# Page_05-LAN9254-Part2.net
KiCad netlist of a schematic drawn in Altium Designer
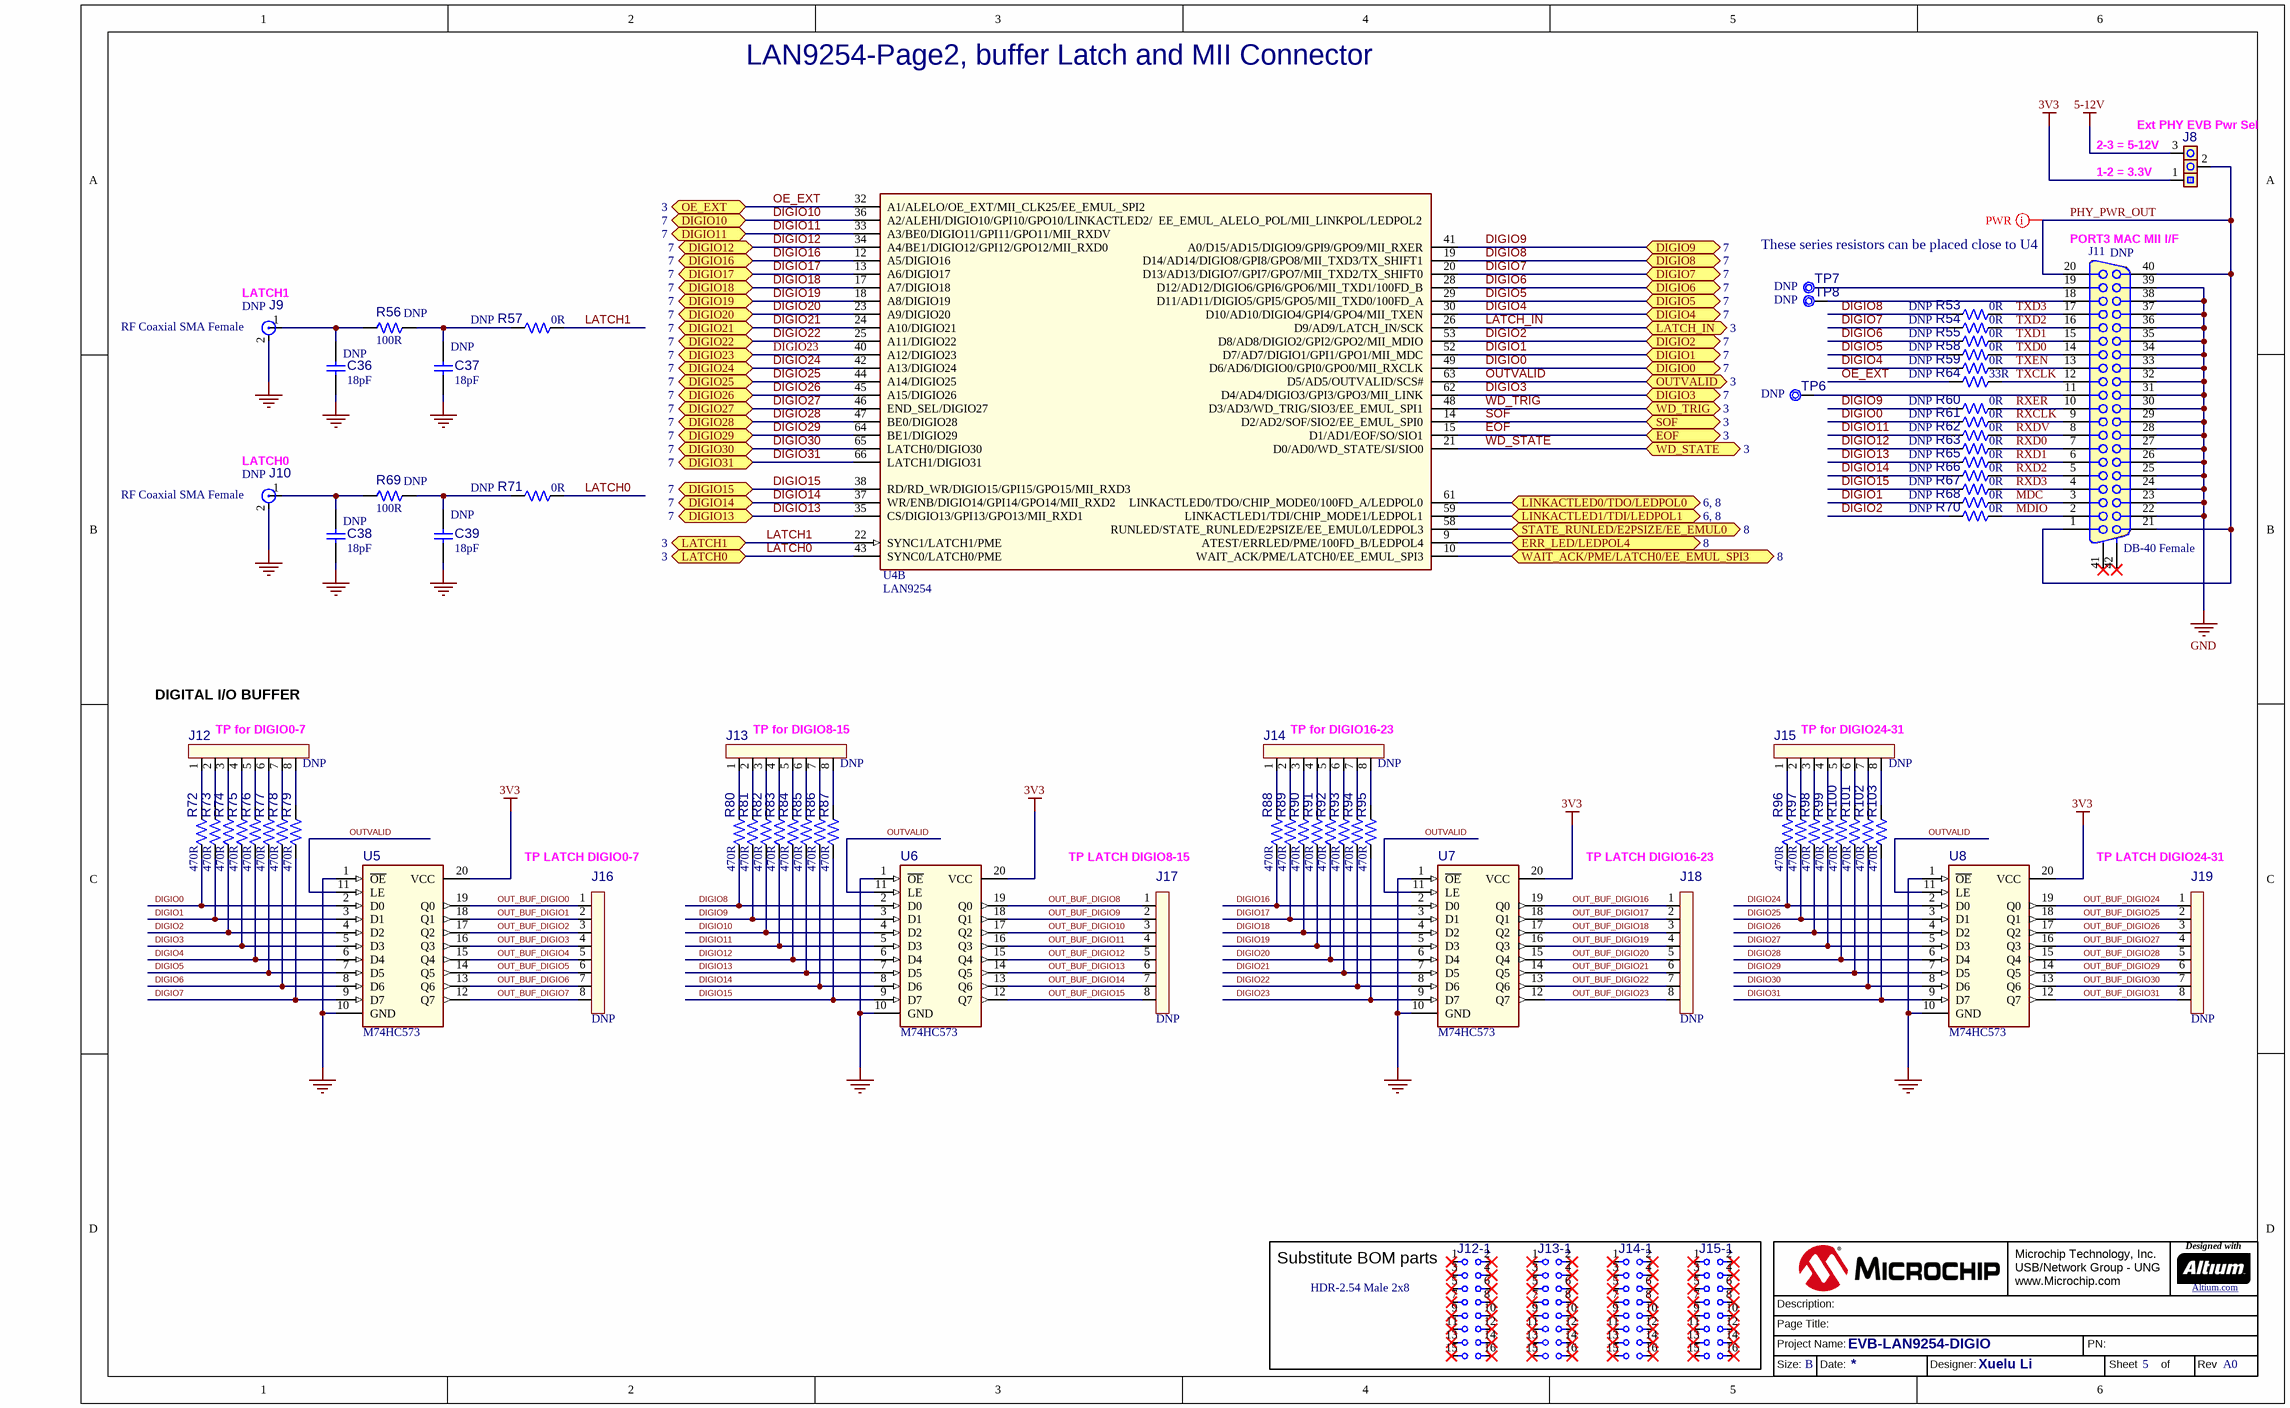
[diagram p0: Page 05-LAN9254-Part2.SchDoc]

(export (version "E")
  (design (tool "Eeschema 10.0.6"))
  (components
    (comp (ref "C36")
      (value "18pF")
      (footprint "CAP_C_0805")
      (description "Capacitor")
      (fields (field (name "VOLTAGE") "50V") (field (name "TOLERANCE") "5%") (field (name "POPULATED") "DNP"))
      (libsource (lib "MCHP-CDB") (part "Capacitor NP"))
    )
    (comp (ref "C37")
      (value "18pF")
      (footprint "CAP_C_0805")
      (description "Capacitor")
      (fields (field (name "VOLTAGE") "50V") (field (name "TOLERANCE") "5%") (field (name "POPULATED") "DNP"))
      (libsource (lib "MCHP-CDB") (part "Capacitor NP"))
    )
    (comp (ref "C38")
      (value "18pF")
      (footprint "CAP_C_0805")
      (description "Capacitor")
      (fields (field (name "VOLTAGE") "50V") (field (name "TOLERANCE") "5%") (field (name "POPULATED") "DNP"))
      (libsource (lib "MCHP-CDB") (part "Capacitor NP"))
    )
    (comp (ref "C39")
      (value "18pF")
      (footprint "CAP_C_0805")
      (description "Capacitor")
      (fields (field (name "VOLTAGE") "50V") (field (name "TOLERANCE") "5%") (field (name "POPULATED") "DNP"))
      (libsource (lib "MCHP-CDB") (part "Capacitor NP"))
    )
    (comp (ref "J8")
      (value "Header 1x3")
      (footprint "HDR_M_2.54_1x3")
      (libsource (lib "MCHP-CDB") (part "Header 1x3"))
    )
    (comp (ref "J9")
      (value "RF Coaxial SMA Female")
      (footprint "CON_JACK_F_TH_V_ACP_901-144-8RFX")
      (description "CON Jack 2 Pins")
      (fields (field (name "POPULATED") "DNP") (field (name "OWNER") "Jairuz Agang-ang"))
      (libsource (lib "MCHP-CDB") (part "CON Jack 2 Pins"))
    )
    (comp (ref "J10")
      (value "RF Coaxial SMA Female")
      (footprint "CON_JACK_F_TH_V_ACP_901-144-8RFX")
      (description "CON Jack 2 Pins")
      (fields (field (name "POPULATED") "DNP") (field (name "OWNER") "Jairuz Agang-ang"))
      (libsource (lib "MCHP-CDB") (part "CON Jack 2 Pins"))
    )
    (comp (ref "J11")
      (value "DB-40 Female")
      (footprint "CON_DSUB40_TH_RA_F")
      (fields
        (field (name "VOLTAGE") "30V")
        (field (name "POPULATED") "DNP")
        (field (name "Comment") "CON DB-40")
        (field (name "OWNER") "Sam Charles")
      )
      (libsource (lib "MCHP-CDB") (part "CON DB-40"))
    )
    (comp (ref "J12")
      (value "HDR_M_2.54_1x8-doubled")
      (footprint "HDR_M_2.54_1x8-doubled")
      (description "CON HDR-2.54 Female 1x8 Gold TH")
      (fields (field (name "POPULATED") "DNP"))
      (libsource (lib "") (part "Header 1x8_1"))
    )
    (comp (ref "J12-1")
      (value "HDR-2.54 Male 2x8")
      (footprint "HDR_M_2.54_2x8")
      (fields (field (name "Comment") "Header 2x8") (field (name "OWNER") "Brent Lanphear"))
      (libsource (lib "MCHP-CDB-Offline") (part "Header 2x8"))
    )
    (comp (ref "J13")
      (value "HDR_M_2.54_1x8-doubled")
      (footprint "HDR_M_2.54_1x8-doubled")
      (description "CON HDR-2.54 Female 1x8 Gold TH")
      (fields (field (name "POPULATED") "DNP"))
      (libsource (lib "") (part "Header 1x8_1"))
    )
    (comp (ref "J13-1")
      (value "Header 2x8")
      (footprint "HDR_M_2.54_2x8")
      (fields (field (name "OWNER") "Brent Lanphear"))
      (libsource (lib "MCHP-CDB-Offline") (part "Header 2x8"))
    )
    (comp (ref "J14")
      (value "HDR_M_2.54_1x8-doubled")
      (footprint "HDR_M_2.54_1x8-doubled")
      (description "CON HDR-2.54 Female 1x8 Gold TH")
      (fields (field (name "POPULATED") "DNP"))
      (libsource (lib "") (part "Header 1x8_1"))
    )
    (comp (ref "J14-1")
      (value "Header 2x8")
      (footprint "HDR_M_2.54_2x8")
      (fields (field (name "OWNER") "Brent Lanphear"))
      (libsource (lib "MCHP-CDB-Offline") (part "Header 2x8"))
    )
    (comp (ref "J15")
      (value "HDR_M_2.54_1x8-doubled")
      (footprint "HDR_M_2.54_1x8-doubled")
      (description "CON HDR-2.54 Female 1x8 Gold TH")
      (fields (field (name "POPULATED") "DNP"))
      (libsource (lib "") (part "Header 1x8_1"))
    )
    (comp (ref "J15-1")
      (value "Header 2x8")
      (footprint "HDR_M_2.54_2x8")
      (fields (field (name "OWNER") "Brent Lanphear"))
      (libsource (lib "MCHP-CDB-Offline") (part "Header 2x8"))
    )
    (comp (ref "J16")
      (value "HDR_M_2.54_1x8-stripped")
      (footprint "HDR_M_2.54_1x8-stripped")
      (description "CON HDR-2.54 Female 1x8 Gold TH")
      (fields (field (name "POPULATED") "DNP"))
      (libsource (lib "MCHP-CDB") (part "Header 1x8"))
    )
    (comp (ref "J17")
      (value "HDR_M_2.54_1x8-stripped")
      (footprint "HDR_M_2.54_1x8-stripped")
      (description "CON HDR-2.54 Female 1x8 Gold TH")
      (fields (field (name "POPULATED") "DNP"))
      (libsource (lib "MCHP-CDB") (part "Header 1x8"))
    )
    (comp (ref "J18")
      (value "HDR_M_2.54_1x8-stripped")
      (footprint "HDR_M_2.54_1x8-stripped")
      (description "CON HDR-2.54 Female 1x8 Gold TH")
      (fields (field (name "POPULATED") "DNP"))
      (libsource (lib "MCHP-CDB") (part "Header 1x8"))
    )
    (comp (ref "J19")
      (value "HDR_M_2.54_1x8-stripped")
      (footprint "HDR_M_2.54_1x8-stripped")
      (description "CON HDR-2.54 Female 1x8 Gold TH")
      (fields (field (name "POPULATED") "DNP"))
      (libsource (lib "MCHP-CDB") (part "Header 1x8"))
    )
    (comp (ref "R53")
      (value "0R")
      (footprint "RES_C_0402")
      (description "Resistor")
      (fields
        (field (name "POWER") "1/16W")
        (field (name "POPULATED") "DNP")
        (field (name "OWNER") "Sompoch Loboonlert")
      )
      (libsource (lib "MCHP-CDB") (part "Resistor"))
    )
    (comp (ref "R54")
      (value "0R")
      (footprint "RES_C_0402")
      (description "Resistor")
      (fields
        (field (name "POWER") "1/16W")
        (field (name "POPULATED") "DNP")
        (field (name "OWNER") "Sompoch Loboonlert")
      )
      (libsource (lib "MCHP-CDB") (part "Resistor"))
    )
    (comp (ref "R55")
      (value "0R")
      (footprint "RES_C_0402")
      (description "Resistor")
      (fields
        (field (name "POWER") "1/16W")
        (field (name "POPULATED") "DNP")
        (field (name "OWNER") "Sompoch Loboonlert")
      )
      (libsource (lib "MCHP-CDB") (part "Resistor"))
    )
    (comp (ref "R56")
      (value "100R")
      (footprint "RES_C_0805")
      (description "Resistor")
      (fields
        (field (name "TOLERANCE") "5%")
        (field (name "POWER") "1/10W")
        (field (name "POPULATED") "DNP")
        (field (name "OWNER") "Jairuz Agang-ang")
      )
      (libsource (lib "MCHP-CDB") (part "Resistor"))
    )
    (comp (ref "R57")
      (value "0R")
      (footprint "RES_C_0402")
      (description "Resistor")
      (fields
        (field (name "POWER") "1/16W")
        (field (name "POPULATED") "DNP")
        (field (name "OWNER") "Sompoch Loboonlert")
      )
      (libsource (lib "MCHP-CDB") (part "Resistor"))
    )
    (comp (ref "R58")
      (value "0R")
      (footprint "RES_C_0402")
      (description "Resistor")
      (fields
        (field (name "POWER") "1/16W")
        (field (name "POPULATED") "DNP")
        (field (name "OWNER") "Sompoch Loboonlert")
      )
      (libsource (lib "MCHP-CDB") (part "Resistor"))
    )
    (comp (ref "R59")
      (value "0R")
      (footprint "RES_C_0402")
      (description "Resistor")
      (fields
        (field (name "POWER") "1/16W")
        (field (name "POPULATED") "DNP")
        (field (name "OWNER") "Sompoch Loboonlert")
      )
      (libsource (lib "MCHP-CDB") (part "Resistor"))
    )
    (comp (ref "R60")
      (value "0R")
      (footprint "RES_C_0402")
      (description "Resistor")
      (fields
        (field (name "POWER") "1/16W")
        (field (name "POPULATED") "DNP")
        (field (name "OWNER") "Sompoch Loboonlert")
      )
      (libsource (lib "MCHP-CDB") (part "Resistor"))
    )
    (comp (ref "R61")
      (value "0R")
      (footprint "RES_C_0402")
      (description "Resistor")
      (fields
        (field (name "POWER") "1/16W")
        (field (name "POPULATED") "DNP")
        (field (name "OWNER") "Sompoch Loboonlert")
      )
      (libsource (lib "MCHP-CDB") (part "Resistor"))
    )
    (comp (ref "R62")
      (value "0R")
      (footprint "RES_C_0402")
      (description "Resistor")
      (fields
        (field (name "POWER") "1/16W")
        (field (name "POPULATED") "DNP")
        (field (name "OWNER") "Sompoch Loboonlert")
      )
      (libsource (lib "MCHP-CDB") (part "Resistor"))
    )
    (comp (ref "R63")
      (value "0R")
      (footprint "RES_C_0402")
      (description "Resistor")
      (fields
        (field (name "POWER") "1/16W")
        (field (name "POPULATED") "DNP")
        (field (name "OWNER") "Sompoch Loboonlert")
      )
      (libsource (lib "MCHP-CDB") (part "Resistor"))
    )
    (comp (ref "R64")
      (value "33R")
      (footprint "RES_C_0402")
      (description "Resistor")
      (fields
        (field (name "TOLERANCE") "1%")
        (field (name "VOLTAGE") "50V")
        (field (name "POPULATED") "DNP")
        (field (name "OWNER") "Mike Ragsdale")
      )
      (libsource (lib "MCHP-CDB") (part "Resistor"))
    )
    (comp (ref "R65")
      (value "0R")
      (footprint "RES_C_0402")
      (description "Resistor")
      (fields
        (field (name "POWER") "1/16W")
        (field (name "POPULATED") "DNP")
        (field (name "OWNER") "Sompoch Loboonlert")
      )
      (libsource (lib "MCHP-CDB") (part "Resistor"))
    )
    (comp (ref "R66")
      (value "0R")
      (footprint "RES_C_0402")
      (description "Resistor")
      (fields
        (field (name "POWER") "1/16W")
        (field (name "POPULATED") "DNP")
        (field (name "OWNER") "Sompoch Loboonlert")
      )
      (libsource (lib "MCHP-CDB") (part "Resistor"))
    )
    (comp (ref "R67")
      (value "0R")
      (footprint "RES_C_0402")
      (description "Resistor")
      (fields
        (field (name "POWER") "1/16W")
        (field (name "POPULATED") "DNP")
        (field (name "OWNER") "Sompoch Loboonlert")
      )
      (libsource (lib "MCHP-CDB") (part "Resistor"))
    )
    (comp (ref "R68")
      (value "0R")
      (footprint "RES_C_0402")
      (description "Resistor")
      (fields
        (field (name "POWER") "1/16W")
        (field (name "POPULATED") "DNP")
        (field (name "OWNER") "Sompoch Loboonlert")
      )
      (libsource (lib "MCHP-CDB") (part "Resistor"))
    )
    (comp (ref "R69")
      (value "100R")
      (footprint "RES_C_0805")
      (description "Resistor")
      (fields
        (field (name "TOLERANCE") "5%")
        (field (name "POWER") "1/10W")
        (field (name "POPULATED") "DNP")
        (field (name "OWNER") "Jairuz Agang-ang")
      )
      (libsource (lib "MCHP-CDB") (part "Resistor"))
    )
    (comp (ref "R70")
      (value "0R")
      (footprint "RES_C_0402")
      (description "Resistor")
      (fields
        (field (name "POWER") "1/16W")
        (field (name "POPULATED") "DNP")
        (field (name "OWNER") "Sompoch Loboonlert")
      )
      (libsource (lib "MCHP-CDB") (part "Resistor"))
    )
    (comp (ref "R71")
      (value "0R")
      (footprint "RES_C_0402")
      (description "Resistor")
      (fields
        (field (name "POWER") "1/16W")
        (field (name "POPULATED") "DNP")
        (field (name "OWNER") "Sompoch Loboonlert")
      )
      (libsource (lib "MCHP-CDB") (part "Resistor"))
    )
    (comp (ref "R72")
      (value "470R")
      (footprint "RES_C_0402")
      (description "Resistor")
      (fields (field (name "TOLERANCE") "5%") (field (name "VOLTAGE") "50V"))
      (libsource (lib "MCHP-CDB") (part "Resistor"))
    )
    (comp (ref "R73")
      (value "470R")
      (footprint "RES_C_0402")
      (description "Resistor")
      (fields (field (name "TOLERANCE") "5%") (field (name "VOLTAGE") "50V"))
      (libsource (lib "MCHP-CDB") (part "Resistor"))
    )
    (comp (ref "R74")
      (value "470R")
      (footprint "RES_C_0402")
      (description "Resistor")
      (fields (field (name "TOLERANCE") "5%") (field (name "VOLTAGE") "50V"))
      (libsource (lib "MCHP-CDB") (part "Resistor"))
    )
    (comp (ref "R75")
      (value "470R")
      (footprint "RES_C_0402")
      (description "Resistor")
      (fields (field (name "TOLERANCE") "5%") (field (name "VOLTAGE") "50V"))
      (libsource (lib "MCHP-CDB") (part "Resistor"))
    )
    (comp (ref "R76")
      (value "470R")
      (footprint "RES_C_0402")
      (description "Resistor")
      (fields (field (name "TOLERANCE") "5%") (field (name "VOLTAGE") "50V"))
      (libsource (lib "MCHP-CDB") (part "Resistor"))
    )
    (comp (ref "R77")
      (value "470R")
      (footprint "RES_C_0402")
      (description "Resistor")
      (fields (field (name "TOLERANCE") "5%") (field (name "VOLTAGE") "50V"))
      (libsource (lib "MCHP-CDB") (part "Resistor"))
    )
    (comp (ref "R78")
      (value "470R")
      (footprint "RES_C_0402")
      (description "Resistor")
      (fields (field (name "TOLERANCE") "5%") (field (name "VOLTAGE") "50V"))
      (libsource (lib "MCHP-CDB") (part "Resistor"))
    )
    (comp (ref "R79")
      (value "470R")
      (footprint "RES_C_0402")
      (description "Resistor")
      (fields (field (name "TOLERANCE") "5%") (field (name "VOLTAGE") "50V"))
      (libsource (lib "MCHP-CDB") (part "Resistor"))
    )
    (comp (ref "R80")
      (value "470R")
      (footprint "RES_C_0402")
      (description "Resistor")
      (fields (field (name "TOLERANCE") "5%") (field (name "VOLTAGE") "50V"))
      (libsource (lib "MCHP-CDB") (part "Resistor"))
    )
    (comp (ref "R81")
      (value "470R")
      (footprint "RES_C_0402")
      (description "Resistor")
      (fields (field (name "TOLERANCE") "5%") (field (name "VOLTAGE") "50V"))
      (libsource (lib "MCHP-CDB") (part "Resistor"))
    )
    (comp (ref "R82")
      (value "470R")
      (footprint "RES_C_0402")
      (description "Resistor")
      (fields (field (name "TOLERANCE") "5%") (field (name "VOLTAGE") "50V"))
      (libsource (lib "MCHP-CDB") (part "Resistor"))
    )
    (comp (ref "R83")
      (value "470R")
      (footprint "RES_C_0402")
      (description "Resistor")
      (fields (field (name "TOLERANCE") "5%") (field (name "VOLTAGE") "50V"))
      (libsource (lib "MCHP-CDB") (part "Resistor"))
    )
    (comp (ref "R84")
      (value "470R")
      (footprint "RES_C_0402")
      (description "Resistor")
      (fields (field (name "TOLERANCE") "5%") (field (name "VOLTAGE") "50V"))
      (libsource (lib "MCHP-CDB") (part "Resistor"))
    )
    (comp (ref "R85")
      (value "470R")
      (footprint "RES_C_0402")
      (description "Resistor")
      (fields (field (name "TOLERANCE") "5%") (field (name "VOLTAGE") "50V"))
      (libsource (lib "MCHP-CDB") (part "Resistor"))
    )
    (comp (ref "R86")
      (value "470R")
      (footprint "RES_C_0402")
      (description "Resistor")
      (fields (field (name "TOLERANCE") "5%") (field (name "VOLTAGE") "50V"))
      (libsource (lib "MCHP-CDB") (part "Resistor"))
    )
    (comp (ref "R87")
      (value "470R")
      (footprint "RES_C_0402")
      (description "Resistor")
      (fields (field (name "TOLERANCE") "5%") (field (name "VOLTAGE") "50V"))
      (libsource (lib "MCHP-CDB") (part "Resistor"))
    )
    (comp (ref "R88")
      (value "470R")
      (footprint "RES_C_0402")
      (description "Resistor")
      (fields (field (name "TOLERANCE") "5%") (field (name "VOLTAGE") "50V"))
      (libsource (lib "MCHP-CDB") (part "Resistor"))
    )
    (comp (ref "R89")
      (value "470R")
      (footprint "RES_C_0402")
      (description "Resistor")
      (fields (field (name "TOLERANCE") "5%") (field (name "VOLTAGE") "50V"))
      (libsource (lib "MCHP-CDB") (part "Resistor"))
    )
    (comp (ref "R90")
      (value "470R")
      (footprint "RES_C_0402")
      (description "Resistor")
      (fields (field (name "TOLERANCE") "5%") (field (name "VOLTAGE") "50V"))
      (libsource (lib "MCHP-CDB") (part "Resistor"))
    )
    (comp (ref "R91")
      (value "470R")
      (footprint "RES_C_0402")
      (description "Resistor")
      (fields (field (name "TOLERANCE") "5%") (field (name "VOLTAGE") "50V"))
      (libsource (lib "MCHP-CDB") (part "Resistor"))
    )
    (comp (ref "R92")
      (value "470R")
      (footprint "RES_C_0402")
      (description "Resistor")
      (fields (field (name "TOLERANCE") "5%") (field (name "VOLTAGE") "50V"))
      (libsource (lib "MCHP-CDB") (part "Resistor"))
    )
    (comp (ref "R93")
      (value "470R")
      (footprint "RES_C_0402")
      (description "Resistor")
      (fields (field (name "TOLERANCE") "5%") (field (name "VOLTAGE") "50V"))
      (libsource (lib "MCHP-CDB") (part "Resistor"))
    )
    (comp (ref "R94")
      (value "470R")
      (footprint "RES_C_0402")
      (description "Resistor")
      (fields (field (name "TOLERANCE") "5%") (field (name "VOLTAGE") "50V"))
      (libsource (lib "MCHP-CDB") (part "Resistor"))
    )
    (comp (ref "R95")
      (value "470R")
      (footprint "RES_C_0402")
      (description "Resistor")
      (fields (field (name "TOLERANCE") "5%") (field (name "VOLTAGE") "50V"))
      (libsource (lib "MCHP-CDB") (part "Resistor"))
    )
    (comp (ref "R96")
      (value "470R")
      (footprint "RES_C_0402")
      (description "Resistor")
      (fields (field (name "TOLERANCE") "5%") (field (name "VOLTAGE") "50V"))
      (libsource (lib "MCHP-CDB") (part "Resistor"))
    )
    (comp (ref "R97")
      (value "470R")
      (footprint "RES_C_0402")
      (description "Resistor")
      (fields (field (name "TOLERANCE") "5%") (field (name "VOLTAGE") "50V"))
      (libsource (lib "MCHP-CDB") (part "Resistor"))
    )
    (comp (ref "R98")
      (value "470R")
      (footprint "RES_C_0402")
      (description "Resistor")
      (fields (field (name "TOLERANCE") "5%") (field (name "VOLTAGE") "50V"))
      (libsource (lib "MCHP-CDB") (part "Resistor"))
    )
    (comp (ref "R99")
      (value "470R")
      (footprint "RES_C_0402")
      (description "Resistor")
      (fields (field (name "TOLERANCE") "5%") (field (name "VOLTAGE") "50V"))
      (libsource (lib "MCHP-CDB") (part "Resistor"))
    )
    (comp (ref "R100")
      (value "470R")
      (footprint "RES_C_0402")
      (description "Resistor")
      (fields (field (name "TOLERANCE") "5%") (field (name "VOLTAGE") "50V"))
      (libsource (lib "MCHP-CDB") (part "Resistor"))
    )
    (comp (ref "R101")
      (value "470R")
      (footprint "RES_C_0402")
      (description "Resistor")
      (fields (field (name "TOLERANCE") "5%") (field (name "VOLTAGE") "50V"))
      (libsource (lib "MCHP-CDB") (part "Resistor"))
    )
    (comp (ref "R102")
      (value "470R")
      (footprint "RES_C_0402")
      (description "Resistor")
      (fields (field (name "TOLERANCE") "5%") (field (name "VOLTAGE") "50V"))
      (libsource (lib "MCHP-CDB") (part "Resistor"))
    )
    (comp (ref "R103")
      (value "470R")
      (footprint "RES_C_0402")
      (description "Resistor")
      (fields (field (name "TOLERANCE") "5%") (field (name "VOLTAGE") "50V"))
      (libsource (lib "MCHP-CDB") (part "Resistor"))
    )
    (comp (ref "TP6")
      (value "Test Point No BOM")
      (footprint "TP_1.2x0.7")
      (description "Test Point")
      (fields (field (name "POPULATED") "DNP") (field (name "OWNER") "Bogdan P (M91398)"))
      (libsource (lib "MCHP-CDB") (part "Test Point No BOM"))
    )
    (comp (ref "TP7")
      (value "Test Point No BOM")
      (footprint "TP_1.2x0.7")
      (description "Test Point")
      (fields (field (name "POPULATED") "DNP") (field (name "OWNER") "Bogdan P (M91398)"))
      (libsource (lib "MCHP-CDB") (part "Test Point No BOM"))
    )
    (comp (ref "TP8")
      (value "Test Point No BOM")
      (footprint "TP_1.2x0.7")
      (description "Test Point")
      (fields (field (name "POPULATED") "DNP") (field (name "OWNER") "Bogdan P (M91398)"))
      (libsource (lib "MCHP-CDB") (part "Test Point No BOM"))
    )
    (comp (ref "U4")
      (value "LAN9254")
      (footprint "TQFP-80_12x12_EP6x6")
      (fields (field (name "Comment") "LAN9254-SVB TQFP80") (field (name "OWNER") "Manikandan Balakrishnan"))
      (libsource (lib "MCHP-CDB") (part "LAN9254-SVB TQFP80"))
    )
    (comp (ref "U5")
      (value "M74HC573")
      (footprint "TSSOP-20")
      (fields (field (name "Comment") "74HC573 TSSOP-20") (field (name "OWNER") "Sam Charles"))
      (libsource (lib "MCHP-CDB") (part "74HC573 TSSOP-20"))
    )
    (comp (ref "U6")
      (value "M74HC573")
      (footprint "TSSOP-20")
      (fields (field (name "Comment") "74HC573 TSSOP-20") (field (name "OWNER") "Sam Charles"))
      (libsource (lib "MCHP-CDB") (part "74HC573 TSSOP-20"))
    )
    (comp (ref "U7")
      (value "M74HC573")
      (footprint "TSSOP-20")
      (fields (field (name "Comment") "74HC573 TSSOP-20") (field (name "OWNER") "Sam Charles"))
      (libsource (lib "MCHP-CDB") (part "74HC573 TSSOP-20"))
    )
    (comp (ref "U8")
      (value "M74HC573")
      (footprint "TSSOP-20")
      (fields (field (name "Comment") "74HC573 TSSOP-20") (field (name "OWNER") "Sam Charles"))
      (libsource (lib "MCHP-CDB") (part "74HC573 TSSOP-20"))
    )
  )
  (nets
    (net (code "1") (name "/DIGIO0") (class "Default")
      (node (ref "R61") (pin "1") (pinfunction "1_1") (pintype "passive"))
      (node (ref "R72") (pin "1") (pinfunction "1_1") (pintype "passive"))
      (node (ref "U4") (pin "49") (pinfunction "D6/AD6/DIGIO0/GPI0/GPO0/MII_RXCLK_49") (pintype "passive"))
      (node (ref "U5") (pin "2") (pinfunction "D0_2") (pintype "input"))
    )
    (net (code "2") (name "/DIGIO1") (class "Default")
      (node (ref "R68") (pin "1") (pinfunction "1_1") (pintype "passive"))
      (node (ref "R73") (pin "1") (pinfunction "1_1") (pintype "passive"))
      (node (ref "U4") (pin "52") (pinfunction "D7/AD7/DIGIO1/GPI1/GPO1/MII_MDC_52") (pintype "passive"))
      (node (ref "U5") (pin "3") (pinfunction "D1_3") (pintype "input"))
    )
    (net (code "3") (name "/DIGIO2") (class "Default")
      (node (ref "R70") (pin "1") (pinfunction "1_1") (pintype "passive"))
      (node (ref "R74") (pin "1") (pinfunction "1_1") (pintype "passive"))
      (node (ref "U4") (pin "53") (pinfunction "D8/AD8/DIGIO2/GPI2/GPO2/MII_MDIO_53") (pintype "passive"))
      (node (ref "U5") (pin "4") (pinfunction "D2_4") (pintype "input"))
    )
    (net (code "4") (name "/DIGIO3") (class "Default")
      (node (ref "R75") (pin "1") (pinfunction "1_1") (pintype "passive"))
      (node (ref "U4") (pin "62") (pinfunction "D4/AD4/DIGIO3/GPI3/GPO3/MII_LINK_62") (pintype "passive"))
      (node (ref "U5") (pin "5") (pinfunction "D3_5") (pintype "input"))
    )
    (net (code "5") (name "/DIGIO4") (class "Default")
      (node (ref "R59") (pin "1") (pinfunction "1_1") (pintype "passive"))
      (node (ref "R76") (pin "1") (pinfunction "1_1") (pintype "passive"))
      (node (ref "U4") (pin "30") (pinfunction "D10/AD10/DIGIO4/GPI4/GPO4/MII_TXEN_30") (pintype "passive"))
      (node (ref "U5") (pin "6") (pinfunction "D4_6") (pintype "input"))
    )
    (net (code "6") (name "/DIGIO5") (class "Default")
      (node (ref "R58") (pin "1") (pinfunction "1_1") (pintype "passive"))
      (node (ref "R77") (pin "1") (pinfunction "1_1") (pintype "passive"))
      (node (ref "U4") (pin "29") (pinfunction "D11/AD11/DIGIO5/GPI5/GPO5/MII_TXD0/100FD_A_29") (pintype "passive"))
      (node (ref "U5") (pin "7") (pinfunction "D5_7") (pintype "input"))
    )
    (net (code "7") (name "/DIGIO6") (class "Default")
      (node (ref "R55") (pin "1") (pinfunction "1_1") (pintype "passive"))
      (node (ref "R78") (pin "1") (pinfunction "1_1") (pintype "passive"))
      (node (ref "U4") (pin "28") (pinfunction "D12/AD12/DIGIO6/GPI6/GPO6/MII_TXD1/100FD_B_28") (pintype "passive"))
      (node (ref "U5") (pin "8") (pinfunction "D6_8") (pintype "input"))
    )
    (net (code "8") (name "/DIGIO7") (class "Default")
      (node (ref "R54") (pin "1") (pinfunction "1_1") (pintype "passive"))
      (node (ref "R79") (pin "1") (pinfunction "1_1") (pintype "passive"))
      (node (ref "U4") (pin "20") (pinfunction "D13/AD13/DIGIO7/GPI7/GPO7/MII_TXD2/TX_SHIFT0_20") (pintype "passive"))
      (node (ref "U5") (pin "9") (pinfunction "D7_9") (pintype "input"))
    )
    (net (code "9") (name "/DIGIO8") (class "Default")
      (node (ref "R53") (pin "1") (pinfunction "1_1") (pintype "passive"))
      (node (ref "R80") (pin "1") (pinfunction "1_1") (pintype "passive"))
      (node (ref "U4") (pin "19") (pinfunction "D14/AD14/DIGIO8/GPI8/GPO8/MII_TXD3/TX_SHIFT1_19") (pintype "passive"))
      (node (ref "U6") (pin "2") (pinfunction "D0_2") (pintype "input"))
    )
    (net (code "10") (name "/DIGIO9") (class "Default")
      (node (ref "R60") (pin "1") (pinfunction "1_1") (pintype "passive"))
      (node (ref "R81") (pin "1") (pinfunction "1_1") (pintype "passive"))
      (node (ref "U4") (pin "41") (pinfunction "A0/D15/AD15/DIGIO9/GPI9/GPO9/MII_RXER_41") (pintype "passive"))
      (node (ref "U6") (pin "3") (pinfunction "D1_3") (pintype "input"))
    )
    (net (code "11") (name "/DIGIO10") (class "Default")
      (node (ref "R82") (pin "1") (pinfunction "1_1") (pintype "passive"))
      (node (ref "U4") (pin "36") (pinfunction "A2/ALEHI/DIGIO10/GPI10/GPO10/LINKACTLED2/__EE_EMUL_ALELO_POL/MII_LINKPOL/LEDPOL2_36") (pintype "passive"))
      (node (ref "U6") (pin "4") (pinfunction "D2_4") (pintype "input"))
    )
    (net (code "12") (name "/DIGIO11") (class "Default")
      (node (ref "R62") (pin "1") (pinfunction "1_1") (pintype "passive"))
      (node (ref "R83") (pin "1") (pinfunction "1_1") (pintype "passive"))
      (node (ref "U4") (pin "33") (pinfunction "A3/BE0/DIGIO11/GPI11/GPO11/MII_RXDV_33") (pintype "passive"))
      (node (ref "U6") (pin "5") (pinfunction "D3_5") (pintype "input"))
    )
    (net (code "13") (name "/DIGIO12") (class "Default")
      (node (ref "R63") (pin "1") (pinfunction "1_1") (pintype "passive"))
      (node (ref "R84") (pin "1") (pinfunction "1_1") (pintype "passive"))
      (node (ref "U4") (pin "34") (pinfunction "A4/BE1/DIGIO12/GPI12/GPO12/MII_RXD0_34") (pintype "passive"))
      (node (ref "U6") (pin "6") (pinfunction "D4_6") (pintype "input"))
    )
    (net (code "14") (name "/DIGIO13") (class "Default")
      (node (ref "R65") (pin "1") (pinfunction "1_1") (pintype "passive"))
      (node (ref "R85") (pin "1") (pinfunction "1_1") (pintype "passive"))
      (node (ref "U4") (pin "35") (pinfunction "CS/DIGIO13/GPI13/GPO13/MII_RXD1_35") (pintype "passive"))
      (node (ref "U6") (pin "7") (pinfunction "D5_7") (pintype "input"))
    )
    (net (code "15") (name "/DIGIO14") (class "Default")
      (node (ref "R66") (pin "1") (pinfunction "1_1") (pintype "passive"))
      (node (ref "R86") (pin "1") (pinfunction "1_1") (pintype "passive"))
      (node (ref "U4") (pin "37") (pinfunction "WR/ENB/DIGIO14/GPI14/GPO14/MII_RXD2_37") (pintype "passive"))
      (node (ref "U6") (pin "8") (pinfunction "D6_8") (pintype "input"))
    )
    (net (code "16") (name "/DIGIO15") (class "Default")
      (node (ref "R67") (pin "1") (pinfunction "1_1") (pintype "passive"))
      (node (ref "R87") (pin "1") (pinfunction "1_1") (pintype "passive"))
      (node (ref "U4") (pin "38") (pinfunction "RD/RD_WR/DIGIO15/GPI15/GPO15/MII_RXD3_38") (pintype "passive"))
      (node (ref "U6") (pin "9") (pinfunction "D7_9") (pintype "input"))
    )
    (net (code "17") (name "/DIGIO16") (class "Default")
      (node (ref "R88") (pin "1") (pinfunction "1_1") (pintype "passive"))
      (node (ref "U4") (pin "12") (pinfunction "A5/DIGIO16_12") (pintype "passive"))
      (node (ref "U7") (pin "2") (pinfunction "D0_2") (pintype "input"))
    )
    (net (code "18") (name "/DIGIO17") (class "Default")
      (node (ref "R89") (pin "1") (pinfunction "1_1") (pintype "passive"))
      (node (ref "U4") (pin "13") (pinfunction "A6/DIGIO17_13") (pintype "passive"))
      (node (ref "U7") (pin "3") (pinfunction "D1_3") (pintype "input"))
    )
    (net (code "19") (name "/DIGIO18") (class "Default")
      (node (ref "R90") (pin "1") (pinfunction "1_1") (pintype "passive"))
      (node (ref "U4") (pin "17") (pinfunction "A7/DIGIO18_17") (pintype "passive"))
      (node (ref "U7") (pin "4") (pinfunction "D2_4") (pintype "input"))
    )
    (net (code "20") (name "/DIGIO19") (class "Default")
      (node (ref "R91") (pin "1") (pinfunction "1_1") (pintype "passive"))
      (node (ref "U4") (pin "18") (pinfunction "A8/DIGIO19_18") (pintype "passive"))
      (node (ref "U7") (pin "5") (pinfunction "D3_5") (pintype "input"))
    )
    (net (code "21") (name "/DIGIO20") (class "Default")
      (node (ref "R92") (pin "1") (pinfunction "1_1") (pintype "passive"))
      (node (ref "U4") (pin "23") (pinfunction "A9/DIGIO20_23") (pintype "passive"))
      (node (ref "U7") (pin "6") (pinfunction "D4_6") (pintype "input"))
    )
    (net (code "22") (name "/DIGIO21") (class "Default")
      (node (ref "R93") (pin "1") (pinfunction "1_1") (pintype "passive"))
      (node (ref "U4") (pin "24") (pinfunction "A10/DIGIO21_24") (pintype "passive"))
      (node (ref "U7") (pin "7") (pinfunction "D5_7") (pintype "input"))
    )
    (net (code "23") (name "/DIGIO22") (class "Default")
      (node (ref "R94") (pin "1") (pinfunction "1_1") (pintype "passive"))
      (node (ref "U4") (pin "25") (pinfunction "A11/DIGIO22_25") (pintype "passive"))
      (node (ref "U7") (pin "8") (pinfunction "D6_8") (pintype "input"))
    )
    (net (code "24") (name "/DIGIO23") (class "Default")
      (node (ref "R95") (pin "1") (pinfunction "1_1") (pintype "passive"))
      (node (ref "U4") (pin "40") (pinfunction "A12/DIGIO23_40") (pintype "passive"))
      (node (ref "U7") (pin "9") (pinfunction "D7_9") (pintype "input"))
    )
    (net (code "25") (name "/DIGIO24") (class "Default")
      (node (ref "R96") (pin "1") (pinfunction "1_1") (pintype "passive"))
      (node (ref "U4") (pin "42") (pinfunction "A13/DIGIO24_42") (pintype "passive"))
      (node (ref "U8") (pin "2") (pinfunction "D0_2") (pintype "input"))
    )
    (net (code "26") (name "/DIGIO25") (class "Default")
      (node (ref "R97") (pin "1") (pinfunction "1_1") (pintype "passive"))
      (node (ref "U4") (pin "44") (pinfunction "A14/DIGIO25_44") (pintype "passive"))
      (node (ref "U8") (pin "3") (pinfunction "D1_3") (pintype "input"))
    )
    (net (code "27") (name "/DIGIO26") (class "Default")
      (node (ref "R98") (pin "1") (pinfunction "1_1") (pintype "passive"))
      (node (ref "U4") (pin "45") (pinfunction "A15/DIGIO26_45") (pintype "passive"))
      (node (ref "U8") (pin "4") (pinfunction "D2_4") (pintype "input"))
    )
    (net (code "28") (name "/DIGIO27") (class "Default")
      (node (ref "R99") (pin "1") (pinfunction "1_1") (pintype "passive"))
      (node (ref "U4") (pin "46") (pinfunction "END_SEL/DIGIO27_46") (pintype "passive"))
      (node (ref "U8") (pin "5") (pinfunction "D3_5") (pintype "input"))
    )
    (net (code "29") (name "/DIGIO28") (class "Default")
      (node (ref "R100") (pin "1") (pinfunction "1_1") (pintype "passive"))
      (node (ref "U4") (pin "47") (pinfunction "BE0/DIGIO28_47") (pintype "passive"))
      (node (ref "U8") (pin "6") (pinfunction "D4_6") (pintype "input"))
    )
    (net (code "30") (name "/DIGIO29") (class "Default")
      (node (ref "R101") (pin "1") (pinfunction "1_1") (pintype "passive"))
      (node (ref "U4") (pin "64") (pinfunction "BE1/DIGIO29_64") (pintype "passive"))
      (node (ref "U8") (pin "7") (pinfunction "D5_7") (pintype "input"))
    )
    (net (code "31") (name "/DIGIO30") (class "Default")
      (node (ref "R102") (pin "1") (pinfunction "1_1") (pintype "passive"))
      (node (ref "U4") (pin "65") (pinfunction "LATCH0/DIGIO30_65") (pintype "passive"))
      (node (ref "U8") (pin "8") (pinfunction "D6_8") (pintype "input"))
    )
    (net (code "32") (name "/DIGIO31") (class "Default")
      (node (ref "R103") (pin "1") (pinfunction "1_1") (pintype "passive"))
      (node (ref "U4") (pin "66") (pinfunction "LATCH1/DIGIO31_66") (pintype "passive"))
      (node (ref "U8") (pin "9") (pinfunction "D7_9") (pintype "input"))
    )
    (net (code "33") (name "/EOF") (class "Default")
      (node (ref "U4") (pin "15") (pinfunction "D1/AD1/EOF/SO/SIO1_15") (pintype "passive"))
    )
    (net (code "34") (name "/ERR_LED{slash}LEDPOL4") (class "Default")
      (node (ref "U4") (pin "9") (pinfunction "ATEST/ERRLED/PME/100FD_B/LEDPOL4_9") (pintype "passive"))
    )
    (net (code "35") (name "/LATCH0") (class "Default")
      (node (ref "R71") (pin "2") (pinfunction "2_2") (pintype "passive"))
      (node (ref "U4") (pin "43") (pinfunction "SYNC0/LATCH0/PME_43") (pintype "passive"))
    )
    (net (code "36") (name "/LATCH1") (class "Default")
      (node (ref "R57") (pin "2") (pinfunction "2_2") (pintype "passive"))
      (node (ref "U4") (pin "22") (pinfunction "SYNC1/LATCH1/PME_22") (pintype "input"))
    )
    (net (code "37") (name "/LATCH_IN") (class "Default")
      (node (ref "U4") (pin "26") (pinfunction "D9/AD9/LATCH_IN/SCK_26") (pintype "passive"))
    )
    (net (code "38") (name "/LINKACTLED0{slash}TDO{slash}LEDPOL0") (class "Default")
      (node (ref "U4") (pin "61") (pinfunction "LINKACTLED0/TDO/CHIP_MODE0/100FD_A/LEDPOL0_61") (pintype "passive"))
    )
    (net (code "39") (name "/LINKACTLED1{slash}TDI{slash}LEDPOL1") (class "Default")
      (node (ref "U4") (pin "59") (pinfunction "LINKACTLED1/TDI/CHIP_MODE1/LEDPOL1_59") (pintype "passive"))
    )
    (net (code "40") (name "/MDC") (class "Default")
      (node (ref "J11") (pin "3") (pinfunction "3_3") (pintype "passive"))
      (node (ref "R68") (pin "2") (pinfunction "2_2") (pintype "passive"))
    )
    (net (code "41") (name "/MDIO") (class "Default")
      (node (ref "J11") (pin "2") (pinfunction "2_2") (pintype "passive"))
      (node (ref "R70") (pin "2") (pinfunction "2_2") (pintype "passive"))
    )
    (net (code "42") (name "/OE_EXT") (class "Default")
      (node (ref "R64") (pin "1") (pinfunction "1_1") (pintype "passive"))
      (node (ref "U4") (pin "32") (pinfunction "A1/ALELO/OE_EXT/MII_CLK25/EE_EMUL_SPI2_32") (pintype "passive"))
    )
    (net (code "43") (name "/OUTVALID") (class "Default")
      (node (ref "U4") (pin "63") (pinfunction "D5/AD5/OUTVALID/SCS#_63") (pintype "passive"))
      (node (ref "U5") (pin "11") (pinfunction "LE_11") (pintype "input"))
      (node (ref "U6") (pin "11") (pinfunction "LE_11") (pintype "input"))
      (node (ref "U7") (pin "11") (pinfunction "LE_11") (pintype "input"))
      (node (ref "U8") (pin "11") (pinfunction "LE_11") (pintype "input"))
    )
    (net (code "44") (name "/OUT_BUF_DIGIO0") (class "Default")
      (node (ref "J16") (pin "1") (pinfunction "1_1") (pintype "passive"))
      (node (ref "U5") (pin "19") (pinfunction "Q0_19") (pintype "output"))
    )
    (net (code "45") (name "/OUT_BUF_DIGIO1") (class "Default")
      (node (ref "J16") (pin "2") (pinfunction "2_2") (pintype "passive"))
      (node (ref "U5") (pin "18") (pinfunction "Q1_18") (pintype "output"))
    )
    (net (code "46") (name "/OUT_BUF_DIGIO2") (class "Default")
      (node (ref "J16") (pin "3") (pinfunction "3_3") (pintype "passive"))
      (node (ref "U5") (pin "17") (pinfunction "Q2_17") (pintype "output"))
    )
    (net (code "47") (name "/OUT_BUF_DIGIO3") (class "Default")
      (node (ref "J16") (pin "4") (pinfunction "4_4") (pintype "passive"))
      (node (ref "U5") (pin "16") (pinfunction "Q3_16") (pintype "output"))
    )
    (net (code "48") (name "/OUT_BUF_DIGIO4") (class "Default")
      (node (ref "J16") (pin "5") (pinfunction "5_5") (pintype "passive"))
      (node (ref "U5") (pin "15") (pinfunction "Q4_15") (pintype "output"))
    )
    (net (code "49") (name "/OUT_BUF_DIGIO5") (class "Default")
      (node (ref "J16") (pin "6") (pinfunction "6_6") (pintype "passive"))
      (node (ref "U5") (pin "14") (pinfunction "Q5_14") (pintype "output"))
    )
    (net (code "50") (name "/OUT_BUF_DIGIO6") (class "Default")
      (node (ref "J16") (pin "7") (pinfunction "7_7") (pintype "passive"))
      (node (ref "U5") (pin "13") (pinfunction "Q6_13") (pintype "output"))
    )
    (net (code "51") (name "/OUT_BUF_DIGIO7") (class "Default")
      (node (ref "J16") (pin "8") (pinfunction "8_8") (pintype "passive"))
      (node (ref "U5") (pin "12") (pinfunction "Q7_12") (pintype "output"))
    )
    (net (code "52") (name "/OUT_BUF_DIGIO8") (class "Default")
      (node (ref "J17") (pin "1") (pinfunction "1_1") (pintype "passive"))
      (node (ref "U6") (pin "19") (pinfunction "Q0_19") (pintype "output"))
    )
    (net (code "53") (name "/OUT_BUF_DIGIO9") (class "Default")
      (node (ref "J17") (pin "2") (pinfunction "2_2") (pintype "passive"))
      (node (ref "U6") (pin "18") (pinfunction "Q1_18") (pintype "output"))
    )
    (net (code "54") (name "/OUT_BUF_DIGIO10") (class "Default")
      (node (ref "J17") (pin "3") (pinfunction "3_3") (pintype "passive"))
      (node (ref "U6") (pin "17") (pinfunction "Q2_17") (pintype "output"))
    )
    (net (code "55") (name "/OUT_BUF_DIGIO11") (class "Default")
      (node (ref "J17") (pin "4") (pinfunction "4_4") (pintype "passive"))
      (node (ref "U6") (pin "16") (pinfunction "Q3_16") (pintype "output"))
    )
    (net (code "56") (name "/OUT_BUF_DIGIO12") (class "Default")
      (node (ref "J17") (pin "5") (pinfunction "5_5") (pintype "passive"))
      (node (ref "U6") (pin "15") (pinfunction "Q4_15") (pintype "output"))
    )
    (net (code "57") (name "/OUT_BUF_DIGIO13") (class "Default")
      (node (ref "J17") (pin "6") (pinfunction "6_6") (pintype "passive"))
      (node (ref "U6") (pin "14") (pinfunction "Q5_14") (pintype "output"))
    )
    (net (code "58") (name "/OUT_BUF_DIGIO14") (class "Default")
      (node (ref "J17") (pin "7") (pinfunction "7_7") (pintype "passive"))
      (node (ref "U6") (pin "13") (pinfunction "Q6_13") (pintype "output"))
    )
    (net (code "59") (name "/OUT_BUF_DIGIO15") (class "Default")
      (node (ref "J17") (pin "8") (pinfunction "8_8") (pintype "passive"))
      (node (ref "U6") (pin "12") (pinfunction "Q7_12") (pintype "output"))
    )
    (net (code "60") (name "/OUT_BUF_DIGIO16") (class "Default")
      (node (ref "J18") (pin "1") (pinfunction "1_1") (pintype "passive"))
      (node (ref "U7") (pin "19") (pinfunction "Q0_19") (pintype "output"))
    )
    (net (code "61") (name "/OUT_BUF_DIGIO17") (class "Default")
      (node (ref "J18") (pin "2") (pinfunction "2_2") (pintype "passive"))
      (node (ref "U7") (pin "18") (pinfunction "Q1_18") (pintype "output"))
    )
    (net (code "62") (name "/OUT_BUF_DIGIO18") (class "Default")
      (node (ref "J18") (pin "3") (pinfunction "3_3") (pintype "passive"))
      (node (ref "U7") (pin "17") (pinfunction "Q2_17") (pintype "output"))
    )
    (net (code "63") (name "/OUT_BUF_DIGIO19") (class "Default")
      (node (ref "J18") (pin "4") (pinfunction "4_4") (pintype "passive"))
      (node (ref "U7") (pin "16") (pinfunction "Q3_16") (pintype "output"))
    )
    (net (code "64") (name "/OUT_BUF_DIGIO20") (class "Default")
      (node (ref "J18") (pin "5") (pinfunction "5_5") (pintype "passive"))
      (node (ref "U7") (pin "15") (pinfunction "Q4_15") (pintype "output"))
    )
    (net (code "65") (name "/OUT_BUF_DIGIO21") (class "Default")
      (node (ref "J18") (pin "6") (pinfunction "6_6") (pintype "passive"))
      (node (ref "U7") (pin "14") (pinfunction "Q5_14") (pintype "output"))
    )
    (net (code "66") (name "/OUT_BUF_DIGIO22") (class "Default")
      (node (ref "J18") (pin "7") (pinfunction "7_7") (pintype "passive"))
      (node (ref "U7") (pin "13") (pinfunction "Q6_13") (pintype "output"))
    )
    (net (code "67") (name "/OUT_BUF_DIGIO23") (class "Default")
      (node (ref "J18") (pin "8") (pinfunction "8_8") (pintype "passive"))
      (node (ref "U7") (pin "12") (pinfunction "Q7_12") (pintype "output"))
    )
    (net (code "68") (name "/OUT_BUF_DIGIO24") (class "Default")
      (node (ref "J19") (pin "1") (pinfunction "1_1") (pintype "passive"))
      (node (ref "U8") (pin "19") (pinfunction "Q0_19") (pintype "output"))
    )
    (net (code "69") (name "/OUT_BUF_DIGIO25") (class "Default")
      (node (ref "J19") (pin "2") (pinfunction "2_2") (pintype "passive"))
      (node (ref "U8") (pin "18") (pinfunction "Q1_18") (pintype "output"))
    )
    (net (code "70") (name "/OUT_BUF_DIGIO26") (class "Default")
      (node (ref "J19") (pin "3") (pinfunction "3_3") (pintype "passive"))
      (node (ref "U8") (pin "17") (pinfunction "Q2_17") (pintype "output"))
    )
    (net (code "71") (name "/OUT_BUF_DIGIO27") (class "Default")
      (node (ref "J19") (pin "4") (pinfunction "4_4") (pintype "passive"))
      (node (ref "U8") (pin "16") (pinfunction "Q3_16") (pintype "output"))
    )
    (net (code "72") (name "/OUT_BUF_DIGIO28") (class "Default")
      (node (ref "J19") (pin "5") (pinfunction "5_5") (pintype "passive"))
      (node (ref "U8") (pin "15") (pinfunction "Q4_15") (pintype "output"))
    )
    (net (code "73") (name "/OUT_BUF_DIGIO29") (class "Default")
      (node (ref "J19") (pin "6") (pinfunction "6_6") (pintype "passive"))
      (node (ref "U8") (pin "14") (pinfunction "Q5_14") (pintype "output"))
    )
    (net (code "74") (name "/OUT_BUF_DIGIO30") (class "Default")
      (node (ref "J19") (pin "7") (pinfunction "7_7") (pintype "passive"))
      (node (ref "U8") (pin "13") (pinfunction "Q6_13") (pintype "output"))
    )
    (net (code "75") (name "/OUT_BUF_DIGIO31") (class "Default")
      (node (ref "J19") (pin "8") (pinfunction "8_8") (pintype "passive"))
      (node (ref "U8") (pin "12") (pinfunction "Q7_12") (pintype "output"))
    )
    (net (code "76") (name "/PHY_PWR_OUT") (class "Default")
      (node (ref "J11") (pin "1") (pinfunction "1_1") (pintype "passive"))
      (node (ref "J11") (pin "20") (pinfunction "20_20") (pintype "passive"))
      (node (ref "J11") (pin "21") (pinfunction "21_21") (pintype "passive"))
      (node (ref "J11") (pin "40") (pinfunction "40_40") (pintype "passive"))
      (node (ref "J8") (pin "2") (pinfunction "2_2") (pintype "passive"))
    )
    (net (code "77") (name "/RXCLK") (class "Default")
      (node (ref "J11") (pin "9") (pinfunction "9_9") (pintype "passive"))
      (node (ref "R61") (pin "2") (pinfunction "2_2") (pintype "passive"))
    )
    (net (code "78") (name "/RXD0") (class "Default")
      (node (ref "J11") (pin "7") (pinfunction "7_7") (pintype "passive"))
      (node (ref "R63") (pin "2") (pinfunction "2_2") (pintype "passive"))
    )
    (net (code "79") (name "/RXD1") (class "Default")
      (node (ref "J11") (pin "6") (pinfunction "6_6") (pintype "passive"))
      (node (ref "R65") (pin "2") (pinfunction "2_2") (pintype "passive"))
    )
    (net (code "80") (name "/RXD2") (class "Default")
      (node (ref "J11") (pin "5") (pinfunction "5_5") (pintype "passive"))
      (node (ref "R66") (pin "2") (pinfunction "2_2") (pintype "passive"))
    )
    (net (code "81") (name "/RXD3") (class "Default")
      (node (ref "J11") (pin "4") (pinfunction "4_4") (pintype "passive"))
      (node (ref "R67") (pin "2") (pinfunction "2_2") (pintype "passive"))
    )
    (net (code "82") (name "/RXDV") (class "Default")
      (node (ref "J11") (pin "8") (pinfunction "8_8") (pintype "passive"))
      (node (ref "R62") (pin "2") (pinfunction "2_2") (pintype "passive"))
    )
    (net (code "83") (name "/RXER") (class "Default")
      (node (ref "J11") (pin "10") (pinfunction "10_10") (pintype "passive"))
      (node (ref "R60") (pin "2") (pinfunction "2_2") (pintype "passive"))
    )
    (net (code "84") (name "/SOF") (class "Default")
      (node (ref "U4") (pin "14") (pinfunction "D2/AD2/SOF/SIO2/EE_EMUL_SPI0_14") (pintype "passive"))
    )
    (net (code "85") (name "/STATE_RUNLED{slash}E2PSIZE{slash}EE_EMUL0") (class "Default")
      (node (ref "U4") (pin "58") (pinfunction "RUNLED/STATE_RUNLED/E2PSIZE/EE_EMUL0/LEDPOL3_58") (pintype "passive"))
    )
    (net (code "86") (name "/TXCLK") (class "Default")
      (node (ref "J11") (pin "12") (pinfunction "12_12") (pintype "passive"))
      (node (ref "R64") (pin "2") (pinfunction "2_2") (pintype "passive"))
    )
    (net (code "87") (name "/TXD0") (class "Default")
      (node (ref "J11") (pin "14") (pinfunction "14_14") (pintype "passive"))
      (node (ref "R58") (pin "2") (pinfunction "2_2") (pintype "passive"))
    )
    (net (code "88") (name "/TXD1") (class "Default")
      (node (ref "J11") (pin "15") (pinfunction "15_15") (pintype "passive"))
      (node (ref "R55") (pin "2") (pinfunction "2_2") (pintype "passive"))
    )
    (net (code "89") (name "/TXD2") (class "Default")
      (node (ref "J11") (pin "16") (pinfunction "16_16") (pintype "passive"))
      (node (ref "R54") (pin "2") (pinfunction "2_2") (pintype "passive"))
    )
    (net (code "90") (name "/TXD3") (class "Default")
      (node (ref "J11") (pin "17") (pinfunction "17_17") (pintype "passive"))
      (node (ref "R53") (pin "2") (pinfunction "2_2") (pintype "passive"))
    )
    (net (code "91") (name "/TXEN") (class "Default")
      (node (ref "J11") (pin "13") (pinfunction "13_13") (pintype "passive"))
      (node (ref "R59") (pin "2") (pinfunction "2_2") (pintype "passive"))
    )
    (net (code "92") (name "/WAIT_ACK{slash}PME{slash}LATCH0{slash}EE_EMUL_SPI3") (class "Default")
      (node (ref "U4") (pin "10") (pinfunction "WAIT_ACK/PME/LATCH0/EE_EMUL_SPI3_10") (pintype "passive"))
    )
    (net (code "93") (name "/WD_STATE") (class "Default")
      (node (ref "U4") (pin "21") (pinfunction "D0/AD0/WD_STATE/SI/SIO0_21") (pintype "passive"))
    )
    (net (code "94") (name "/WD_TRIG") (class "Default")
      (node (ref "U4") (pin "48") (pinfunction "D3/AD3/WD_TRIG/SIO3/EE_EMUL_SPI1_48") (pintype "passive"))
    )
    (net (code "95") (name "3V3") (class "Default")
      (node (ref "J8") (pin "1") (pinfunction "1_1") (pintype "passive"))
      (node (ref "U5") (pin "20") (pinfunction "VCC_20") (pintype "power_in"))
      (node (ref "U6") (pin "20") (pinfunction "VCC_20") (pintype "power_in"))
      (node (ref "U7") (pin "20") (pinfunction "VCC_20") (pintype "power_in"))
      (node (ref "U8") (pin "20") (pinfunction "VCC_20") (pintype "power_in"))
    )
    (net (code "96") (name "5-12V") (class "Default")
      (node (ref "J8") (pin "3") (pinfunction "3_3") (pintype "passive"))
    )
    (net (code "97") (name "GND") (class "Default")
      (node (ref "C36") (pin "1") (pinfunction "1_1") (pintype "passive"))
      (node (ref "C37") (pin "1") (pinfunction "1_1") (pintype "passive"))
      (node (ref "C38") (pin "1") (pinfunction "1_1") (pintype "passive"))
      (node (ref "C39") (pin "1") (pinfunction "1_1") (pintype "passive"))
      (node (ref "J10") (pin "2") (pinfunction "2_2") (pintype "passive"))
      (node (ref "J11") (pin "22") (pinfunction "22_22") (pintype "passive"))
      (node (ref "J11") (pin "23") (pinfunction "23_23") (pintype "passive"))
      (node (ref "J11") (pin "24") (pinfunction "24_24") (pintype "passive"))
      (node (ref "J11") (pin "25") (pinfunction "25_25") (pintype "passive"))
      (node (ref "J11") (pin "26") (pinfunction "26_26") (pintype "passive"))
      (node (ref "J11") (pin "27") (pinfunction "27_27") (pintype "passive"))
      (node (ref "J11") (pin "28") (pinfunction "28_28") (pintype "passive"))
      (node (ref "J11") (pin "29") (pinfunction "29_29") (pintype "passive"))
      (node (ref "J11") (pin "30") (pinfunction "30_30") (pintype "passive"))
      (node (ref "J11") (pin "31") (pinfunction "31_31") (pintype "passive"))
      (node (ref "J11") (pin "32") (pinfunction "32_32") (pintype "passive"))
      (node (ref "J11") (pin "33") (pinfunction "33_33") (pintype "passive"))
      (node (ref "J11") (pin "34") (pinfunction "34_34") (pintype "passive"))
      (node (ref "J11") (pin "35") (pinfunction "35_35") (pintype "passive"))
      (node (ref "J11") (pin "36") (pinfunction "36_36") (pintype "passive"))
      (node (ref "J11") (pin "37") (pinfunction "37_37") (pintype "passive"))
      (node (ref "J11") (pin "38") (pinfunction "38_38") (pintype "passive"))
      (node (ref "J11") (pin "39") (pinfunction "39_39") (pintype "passive"))
      (node (ref "J9") (pin "2") (pinfunction "2_2") (pintype "passive"))
      (node (ref "U5") (pin "1") (pinfunction "~{OE}_1") (pintype "input"))
      (node (ref "U5") (pin "10") (pinfunction "GND_10") (pintype "passive"))
      (node (ref "U6") (pin "1") (pinfunction "~{OE}_1") (pintype "input"))
      (node (ref "U6") (pin "10") (pinfunction "GND_10") (pintype "passive"))
      (node (ref "U7") (pin "1") (pinfunction "~{OE}_1") (pintype "input"))
      (node (ref "U7") (pin "10") (pinfunction "GND_10") (pintype "passive"))
      (node (ref "U8") (pin "1") (pinfunction "~{OE}_1") (pintype "input"))
      (node (ref "U8") (pin "10") (pinfunction "GND_10") (pintype "passive"))
    )
    (net (code "98") (name "Net-(C36-Pad2)") (class "Default")
      (node (ref "C36") (pin "2") (pinfunction "2_2") (pintype "passive"))
      (node (ref "J9") (pin "1") (pinfunction "1_1") (pintype "passive"))
      (node (ref "R56") (pin "1") (pinfunction "1_1") (pintype "passive"))
    )
    (net (code "99") (name "Net-(C37-Pad2)") (class "Default")
      (node (ref "C37") (pin "2") (pinfunction "2_2") (pintype "passive"))
      (node (ref "R56") (pin "2") (pinfunction "2_2") (pintype "passive"))
      (node (ref "R57") (pin "1") (pinfunction "1_1") (pintype "passive"))
    )
    (net (code "100") (name "Net-(C38-Pad2)") (class "Default")
      (node (ref "C38") (pin "2") (pinfunction "2_2") (pintype "passive"))
      (node (ref "J10") (pin "1") (pinfunction "1_1") (pintype "passive"))
      (node (ref "R69") (pin "1") (pinfunction "1_1") (pintype "passive"))
    )
    (net (code "101") (name "Net-(C39-Pad2)") (class "Default")
      (node (ref "C39") (pin "2") (pinfunction "2_2") (pintype "passive"))
      (node (ref "R69") (pin "2") (pinfunction "2_2") (pintype "passive"))
      (node (ref "R71") (pin "1") (pinfunction "1_1") (pintype "passive"))
    )
    (net (code "102") (name "Net-(J11-Pad11)") (class "Default")
      (node (ref "J11") (pin "11") (pinfunction "11_11") (pintype "passive"))
      (node (ref "TP6") (pin "1") (pinfunction "1_1") (pintype "passive"))
    )
    (net (code "103") (name "Net-(J11-Pad18)") (class "Default")
      (node (ref "J11") (pin "18") (pinfunction "18_18") (pintype "passive"))
      (node (ref "TP8") (pin "1") (pinfunction "1_1") (pintype "passive"))
    )
    (net (code "104") (name "Net-(J11-Pad19)") (class "Default")
      (node (ref "J11") (pin "19") (pinfunction "19_19") (pintype "passive"))
      (node (ref "TP7") (pin "1") (pinfunction "1_1") (pintype "passive"))
    )
    (net (code "105") (name "Net-(J12-Pad1)") (class "Default")
      (node (ref "J12") (pin "1") (pinfunction "1_1") (pintype "passive"))
      (node (ref "R72") (pin "2") (pinfunction "2_2") (pintype "passive"))
    )
    (net (code "106") (name "Net-(J12-Pad2)") (class "Default")
      (node (ref "J12") (pin "2") (pinfunction "2_2") (pintype "passive"))
      (node (ref "R73") (pin "2") (pinfunction "2_2") (pintype "passive"))
    )
    (net (code "107") (name "Net-(J12-Pad3)") (class "Default")
      (node (ref "J12") (pin "3") (pinfunction "3_3") (pintype "passive"))
      (node (ref "R74") (pin "2") (pinfunction "2_2") (pintype "passive"))
    )
    (net (code "108") (name "Net-(J12-Pad4)") (class "Default")
      (node (ref "J12") (pin "4") (pinfunction "4_4") (pintype "passive"))
      (node (ref "R75") (pin "2") (pinfunction "2_2") (pintype "passive"))
    )
    (net (code "109") (name "Net-(J12-Pad5)") (class "Default")
      (node (ref "J12") (pin "5") (pinfunction "5_5") (pintype "passive"))
      (node (ref "R76") (pin "2") (pinfunction "2_2") (pintype "passive"))
    )
    (net (code "110") (name "Net-(J12-Pad6)") (class "Default")
      (node (ref "J12") (pin "6") (pinfunction "6_6") (pintype "passive"))
      (node (ref "R77") (pin "2") (pinfunction "2_2") (pintype "passive"))
    )
    (net (code "111") (name "Net-(J12-Pad7)") (class "Default")
      (node (ref "J12") (pin "7") (pinfunction "7_7") (pintype "passive"))
      (node (ref "R78") (pin "2") (pinfunction "2_2") (pintype "passive"))
    )
    (net (code "112") (name "Net-(J12-Pad8)") (class "Default")
      (node (ref "J12") (pin "8") (pinfunction "8_8") (pintype "passive"))
      (node (ref "R79") (pin "2") (pinfunction "2_2") (pintype "passive"))
    )
    (net (code "113") (name "Net-(J13-Pad1)") (class "Default")
      (node (ref "J13") (pin "1") (pinfunction "1_1") (pintype "passive"))
      (node (ref "R80") (pin "2") (pinfunction "2_2") (pintype "passive"))
    )
    (net (code "114") (name "Net-(J13-Pad2)") (class "Default")
      (node (ref "J13") (pin "2") (pinfunction "2_2") (pintype "passive"))
      (node (ref "R81") (pin "2") (pinfunction "2_2") (pintype "passive"))
    )
    (net (code "115") (name "Net-(J13-Pad3)") (class "Default")
      (node (ref "J13") (pin "3") (pinfunction "3_3") (pintype "passive"))
      (node (ref "R82") (pin "2") (pinfunction "2_2") (pintype "passive"))
    )
    (net (code "116") (name "Net-(J13-Pad4)") (class "Default")
      (node (ref "J13") (pin "4") (pinfunction "4_4") (pintype "passive"))
      (node (ref "R83") (pin "2") (pinfunction "2_2") (pintype "passive"))
    )
    (net (code "117") (name "Net-(J13-Pad5)") (class "Default")
      (node (ref "J13") (pin "5") (pinfunction "5_5") (pintype "passive"))
      (node (ref "R84") (pin "2") (pinfunction "2_2") (pintype "passive"))
    )
    (net (code "118") (name "Net-(J13-Pad6)") (class "Default")
      (node (ref "J13") (pin "6") (pinfunction "6_6") (pintype "passive"))
      (node (ref "R85") (pin "2") (pinfunction "2_2") (pintype "passive"))
    )
    (net (code "119") (name "Net-(J13-Pad7)") (class "Default")
      (node (ref "J13") (pin "7") (pinfunction "7_7") (pintype "passive"))
      (node (ref "R86") (pin "2") (pinfunction "2_2") (pintype "passive"))
    )
    (net (code "120") (name "Net-(J13-Pad8)") (class "Default")
      (node (ref "J13") (pin "8") (pinfunction "8_8") (pintype "passive"))
      (node (ref "R87") (pin "2") (pinfunction "2_2") (pintype "passive"))
    )
    (net (code "121") (name "Net-(J14-Pad1)") (class "Default")
      (node (ref "J14") (pin "1") (pinfunction "1_1") (pintype "passive"))
      (node (ref "R88") (pin "2") (pinfunction "2_2") (pintype "passive"))
    )
    (net (code "122") (name "Net-(J14-Pad2)") (class "Default")
      (node (ref "J14") (pin "2") (pinfunction "2_2") (pintype "passive"))
      (node (ref "R89") (pin "2") (pinfunction "2_2") (pintype "passive"))
    )
    (net (code "123") (name "Net-(J14-Pad3)") (class "Default")
      (node (ref "J14") (pin "3") (pinfunction "3_3") (pintype "passive"))
      (node (ref "R90") (pin "2") (pinfunction "2_2") (pintype "passive"))
    )
    (net (code "124") (name "Net-(J14-Pad4)") (class "Default")
      (node (ref "J14") (pin "4") (pinfunction "4_4") (pintype "passive"))
      (node (ref "R91") (pin "2") (pinfunction "2_2") (pintype "passive"))
    )
    (net (code "125") (name "Net-(J14-Pad5)") (class "Default")
      (node (ref "J14") (pin "5") (pinfunction "5_5") (pintype "passive"))
      (node (ref "R92") (pin "2") (pinfunction "2_2") (pintype "passive"))
    )
    (net (code "126") (name "Net-(J14-Pad6)") (class "Default")
      (node (ref "J14") (pin "6") (pinfunction "6_6") (pintype "passive"))
      (node (ref "R93") (pin "2") (pinfunction "2_2") (pintype "passive"))
    )
    (net (code "127") (name "Net-(J14-Pad7)") (class "Default")
      (node (ref "J14") (pin "7") (pinfunction "7_7") (pintype "passive"))
      (node (ref "R94") (pin "2") (pinfunction "2_2") (pintype "passive"))
    )
    (net (code "128") (name "Net-(J14-Pad8)") (class "Default")
      (node (ref "J14") (pin "8") (pinfunction "8_8") (pintype "passive"))
      (node (ref "R95") (pin "2") (pinfunction "2_2") (pintype "passive"))
    )
    (net (code "129") (name "Net-(J15-Pad1)") (class "Default")
      (node (ref "J15") (pin "1") (pinfunction "1_1") (pintype "passive"))
      (node (ref "R96") (pin "2") (pinfunction "2_2") (pintype "passive"))
    )
    (net (code "130") (name "Net-(J15-Pad2)") (class "Default")
      (node (ref "J15") (pin "2") (pinfunction "2_2") (pintype "passive"))
      (node (ref "R97") (pin "2") (pinfunction "2_2") (pintype "passive"))
    )
    (net (code "131") (name "Net-(J15-Pad3)") (class "Default")
      (node (ref "J15") (pin "3") (pinfunction "3_3") (pintype "passive"))
      (node (ref "R98") (pin "2") (pinfunction "2_2") (pintype "passive"))
    )
    (net (code "132") (name "Net-(J15-Pad4)") (class "Default")
      (node (ref "J15") (pin "4") (pinfunction "4_4") (pintype "passive"))
      (node (ref "R99") (pin "2") (pinfunction "2_2") (pintype "passive"))
    )
    (net (code "133") (name "Net-(J15-Pad5)") (class "Default")
      (node (ref "J15") (pin "5") (pinfunction "5_5") (pintype "passive"))
      (node (ref "R100") (pin "2") (pinfunction "2_2") (pintype "passive"))
    )
    (net (code "134") (name "Net-(J15-Pad6)") (class "Default")
      (node (ref "J15") (pin "6") (pinfunction "6_6") (pintype "passive"))
      (node (ref "R101") (pin "2") (pinfunction "2_2") (pintype "passive"))
    )
    (net (code "135") (name "Net-(J15-Pad7)") (class "Default")
      (node (ref "J15") (pin "7") (pinfunction "7_7") (pintype "passive"))
      (node (ref "R102") (pin "2") (pinfunction "2_2") (pintype "passive"))
    )
    (net (code "136") (name "Net-(J15-Pad8)") (class "Default")
      (node (ref "J15") (pin "8") (pinfunction "8_8") (pintype "passive"))
      (node (ref "R103") (pin "2") (pinfunction "2_2") (pintype "passive"))
    )
    (net (code "137") (name "unconnected-(J11-Pad41)") (class "Default")
      (node (ref "J11") (pin "41") (pinfunction "41_41") (pintype "passive+no_connect"))
    )
    (net (code "138") (name "unconnected-(J11-Pad42)") (class "Default")
      (node (ref "J11") (pin "42") (pinfunction "42_42") (pintype "passive+no_connect"))
    )
    (net (code "139") (name "unconnected-(J12-1-Pad1)") (class "Default")
      (node (ref "J12-1") (pin "1") (pinfunction "1_1") (pintype "passive+no_connect"))
    )
    (net (code "140") (name "unconnected-(J12-1-Pad2)") (class "Default")
      (node (ref "J12-1") (pin "2") (pinfunction "2_2") (pintype "passive+no_connect"))
    )
    (net (code "141") (name "unconnected-(J12-1-Pad3)") (class "Default")
      (node (ref "J12-1") (pin "3") (pinfunction "3_3") (pintype "passive+no_connect"))
    )
    (net (code "142") (name "unconnected-(J12-1-Pad4)") (class "Default")
      (node (ref "J12-1") (pin "4") (pinfunction "4_4") (pintype "passive+no_connect"))
    )
    (net (code "143") (name "unconnected-(J12-1-Pad5)") (class "Default")
      (node (ref "J12-1") (pin "5") (pinfunction "5_5") (pintype "passive+no_connect"))
    )
    (net (code "144") (name "unconnected-(J12-1-Pad6)") (class "Default")
      (node (ref "J12-1") (pin "6") (pinfunction "6_6") (pintype "passive+no_connect"))
    )
    (net (code "145") (name "unconnected-(J12-1-Pad7)") (class "Default")
      (node (ref "J12-1") (pin "7") (pinfunction "7_7") (pintype "passive+no_connect"))
    )
    (net (code "146") (name "unconnected-(J12-1-Pad8)") (class "Default")
      (node (ref "J12-1") (pin "8") (pinfunction "8_8") (pintype "passive+no_connect"))
    )
    (net (code "147") (name "unconnected-(J12-1-Pad9)") (class "Default")
      (node (ref "J12-1") (pin "9") (pinfunction "9_9") (pintype "passive+no_connect"))
    )
    (net (code "148") (name "unconnected-(J12-1-Pad10)") (class "Default")
      (node (ref "J12-1") (pin "10") (pinfunction "10_10") (pintype "passive+no_connect"))
    )
    (net (code "149") (name "unconnected-(J12-1-Pad11)") (class "Default")
      (node (ref "J12-1") (pin "11") (pinfunction "11_11") (pintype "passive+no_connect"))
    )
    (net (code "150") (name "unconnected-(J12-1-Pad12)") (class "Default")
      (node (ref "J12-1") (pin "12") (pinfunction "12_12") (pintype "passive+no_connect"))
    )
    (net (code "151") (name "unconnected-(J12-1-Pad13)") (class "Default")
      (node (ref "J12-1") (pin "13") (pinfunction "13_13") (pintype "passive+no_connect"))
    )
    (net (code "152") (name "unconnected-(J12-1-Pad14)") (class "Default")
      (node (ref "J12-1") (pin "14") (pinfunction "14_14") (pintype "passive+no_connect"))
    )
    (net (code "153") (name "unconnected-(J12-1-Pad15)") (class "Default")
      (node (ref "J12-1") (pin "15") (pinfunction "15_15") (pintype "passive+no_connect"))
    )
    (net (code "154") (name "unconnected-(J12-1-Pad16)") (class "Default")
      (node (ref "J12-1") (pin "16") (pinfunction "16_16") (pintype "passive+no_connect"))
    )
    (net (code "155") (name "unconnected-(J13-1-Pad1)") (class "Default")
      (node (ref "J13-1") (pin "1") (pinfunction "1_1") (pintype "passive+no_connect"))
    )
    (net (code "156") (name "unconnected-(J13-1-Pad2)") (class "Default")
      (node (ref "J13-1") (pin "2") (pinfunction "2_2") (pintype "passive+no_connect"))
    )
    (net (code "157") (name "unconnected-(J13-1-Pad3)") (class "Default")
      (node (ref "J13-1") (pin "3") (pinfunction "3_3") (pintype "passive+no_connect"))
    )
    (net (code "158") (name "unconnected-(J13-1-Pad4)") (class "Default")
      (node (ref "J13-1") (pin "4") (pinfunction "4_4") (pintype "passive+no_connect"))
    )
    (net (code "159") (name "unconnected-(J13-1-Pad5)") (class "Default")
      (node (ref "J13-1") (pin "5") (pinfunction "5_5") (pintype "passive+no_connect"))
    )
    (net (code "160") (name "unconnected-(J13-1-Pad6)") (class "Default")
      (node (ref "J13-1") (pin "6") (pinfunction "6_6") (pintype "passive+no_connect"))
    )
    (net (code "161") (name "unconnected-(J13-1-Pad7)") (class "Default")
      (node (ref "J13-1") (pin "7") (pinfunction "7_7") (pintype "passive+no_connect"))
    )
    (net (code "162") (name "unconnected-(J13-1-Pad8)") (class "Default")
      (node (ref "J13-1") (pin "8") (pinfunction "8_8") (pintype "passive+no_connect"))
    )
    (net (code "163") (name "unconnected-(J13-1-Pad9)") (class "Default")
      (node (ref "J13-1") (pin "9") (pinfunction "9_9") (pintype "passive+no_connect"))
    )
    (net (code "164") (name "unconnected-(J13-1-Pad10)") (class "Default")
      (node (ref "J13-1") (pin "10") (pinfunction "10_10") (pintype "passive+no_connect"))
    )
    (net (code "165") (name "unconnected-(J13-1-Pad11)") (class "Default")
      (node (ref "J13-1") (pin "11") (pinfunction "11_11") (pintype "passive+no_connect"))
    )
    (net (code "166") (name "unconnected-(J13-1-Pad12)") (class "Default")
      (node (ref "J13-1") (pin "12") (pinfunction "12_12") (pintype "passive+no_connect"))
    )
    (net (code "167") (name "unconnected-(J13-1-Pad13)") (class "Default")
      (node (ref "J13-1") (pin "13") (pinfunction "13_13") (pintype "passive+no_connect"))
    )
    (net (code "168") (name "unconnected-(J13-1-Pad14)") (class "Default")
      (node (ref "J13-1") (pin "14") (pinfunction "14_14") (pintype "passive+no_connect"))
    )
    (net (code "169") (name "unconnected-(J13-1-Pad15)") (class "Default")
      (node (ref "J13-1") (pin "15") (pinfunction "15_15") (pintype "passive+no_connect"))
    )
    (net (code "170") (name "unconnected-(J13-1-Pad16)") (class "Default")
      (node (ref "J13-1") (pin "16") (pinfunction "16_16") (pintype "passive+no_connect"))
    )
    (net (code "171") (name "unconnected-(J14-1-Pad1)") (class "Default")
      (node (ref "J14-1") (pin "1") (pinfunction "1_1") (pintype "passive+no_connect"))
    )
    (net (code "172") (name "unconnected-(J14-1-Pad2)") (class "Default")
      (node (ref "J14-1") (pin "2") (pinfunction "2_2") (pintype "passive+no_connect"))
    )
    (net (code "173") (name "unconnected-(J14-1-Pad3)") (class "Default")
      (node (ref "J14-1") (pin "3") (pinfunction "3_3") (pintype "passive+no_connect"))
    )
    (net (code "174") (name "unconnected-(J14-1-Pad4)") (class "Default")
      (node (ref "J14-1") (pin "4") (pinfunction "4_4") (pintype "passive+no_connect"))
    )
    (net (code "175") (name "unconnected-(J14-1-Pad5)") (class "Default")
      (node (ref "J14-1") (pin "5") (pinfunction "5_5") (pintype "passive+no_connect"))
    )
    (net (code "176") (name "unconnected-(J14-1-Pad6)") (class "Default")
      (node (ref "J14-1") (pin "6") (pinfunction "6_6") (pintype "passive+no_connect"))
    )
    (net (code "177") (name "unconnected-(J14-1-Pad7)") (class "Default")
      (node (ref "J14-1") (pin "7") (pinfunction "7_7") (pintype "passive+no_connect"))
    )
    (net (code "178") (name "unconnected-(J14-1-Pad8)") (class "Default")
      (node (ref "J14-1") (pin "8") (pinfunction "8_8") (pintype "passive+no_connect"))
    )
    (net (code "179") (name "unconnected-(J14-1-Pad9)") (class "Default")
      (node (ref "J14-1") (pin "9") (pinfunction "9_9") (pintype "passive+no_connect"))
    )
    (net (code "180") (name "unconnected-(J14-1-Pad10)") (class "Default")
      (node (ref "J14-1") (pin "10") (pinfunction "10_10") (pintype "passive+no_connect"))
    )
    (net (code "181") (name "unconnected-(J14-1-Pad11)") (class "Default")
      (node (ref "J14-1") (pin "11") (pinfunction "11_11") (pintype "passive+no_connect"))
    )
    (net (code "182") (name "unconnected-(J14-1-Pad12)") (class "Default")
      (node (ref "J14-1") (pin "12") (pinfunction "12_12") (pintype "passive+no_connect"))
    )
    (net (code "183") (name "unconnected-(J14-1-Pad13)") (class "Default")
      (node (ref "J14-1") (pin "13") (pinfunction "13_13") (pintype "passive+no_connect"))
    )
    (net (code "184") (name "unconnected-(J14-1-Pad14)") (class "Default")
      (node (ref "J14-1") (pin "14") (pinfunction "14_14") (pintype "passive+no_connect"))
    )
    (net (code "185") (name "unconnected-(J14-1-Pad15)") (class "Default")
      (node (ref "J14-1") (pin "15") (pinfunction "15_15") (pintype "passive+no_connect"))
    )
    (net (code "186") (name "unconnected-(J14-1-Pad16)") (class "Default")
      (node (ref "J14-1") (pin "16") (pinfunction "16_16") (pintype "passive+no_connect"))
    )
    (net (code "187") (name "unconnected-(J15-1-Pad1)") (class "Default")
      (node (ref "J15-1") (pin "1") (pinfunction "1_1") (pintype "passive+no_connect"))
    )
    (net (code "188") (name "unconnected-(J15-1-Pad2)") (class "Default")
      (node (ref "J15-1") (pin "2") (pinfunction "2_2") (pintype "passive+no_connect"))
    )
    (net (code "189") (name "unconnected-(J15-1-Pad3)") (class "Default")
      (node (ref "J15-1") (pin "3") (pinfunction "3_3") (pintype "passive+no_connect"))
    )
    (net (code "190") (name "unconnected-(J15-1-Pad4)") (class "Default")
      (node (ref "J15-1") (pin "4") (pinfunction "4_4") (pintype "passive+no_connect"))
    )
    (net (code "191") (name "unconnected-(J15-1-Pad5)") (class "Default")
      (node (ref "J15-1") (pin "5") (pinfunction "5_5") (pintype "passive+no_connect"))
    )
    (net (code "192") (name "unconnected-(J15-1-Pad6)") (class "Default")
      (node (ref "J15-1") (pin "6") (pinfunction "6_6") (pintype "passive+no_connect"))
    )
    (net (code "193") (name "unconnected-(J15-1-Pad7)") (class "Default")
      (node (ref "J15-1") (pin "7") (pinfunction "7_7") (pintype "passive+no_connect"))
    )
    (net (code "194") (name "unconnected-(J15-1-Pad8)") (class "Default")
      (node (ref "J15-1") (pin "8") (pinfunction "8_8") (pintype "passive+no_connect"))
    )
    (net (code "195") (name "unconnected-(J15-1-Pad9)") (class "Default")
      (node (ref "J15-1") (pin "9") (pinfunction "9_9") (pintype "passive+no_connect"))
    )
    (net (code "196") (name "unconnected-(J15-1-Pad10)") (class "Default")
      (node (ref "J15-1") (pin "10") (pinfunction "10_10") (pintype "passive+no_connect"))
    )
    (net (code "197") (name "unconnected-(J15-1-Pad11)") (class "Default")
      (node (ref "J15-1") (pin "11") (pinfunction "11_11") (pintype "passive+no_connect"))
    )
    (net (code "198") (name "unconnected-(J15-1-Pad12)") (class "Default")
      (node (ref "J15-1") (pin "12") (pinfunction "12_12") (pintype "passive+no_connect"))
    )
    (net (code "199") (name "unconnected-(J15-1-Pad13)") (class "Default")
      (node (ref "J15-1") (pin "13") (pinfunction "13_13") (pintype "passive+no_connect"))
    )
    (net (code "200") (name "unconnected-(J15-1-Pad14)") (class "Default")
      (node (ref "J15-1") (pin "14") (pinfunction "14_14") (pintype "passive+no_connect"))
    )
    (net (code "201") (name "unconnected-(J15-1-Pad15)") (class "Default")
      (node (ref "J15-1") (pin "15") (pinfunction "15_15") (pintype "passive+no_connect"))
    )
    (net (code "202") (name "unconnected-(J15-1-Pad16)") (class "Default")
      (node (ref "J15-1") (pin "16") (pinfunction "16_16") (pintype "passive+no_connect"))
    )
  )
)
